# CoopCommand_2020-07-27_09-00-17.net
KiCad netlist of a schematic drawn in EasyEDA
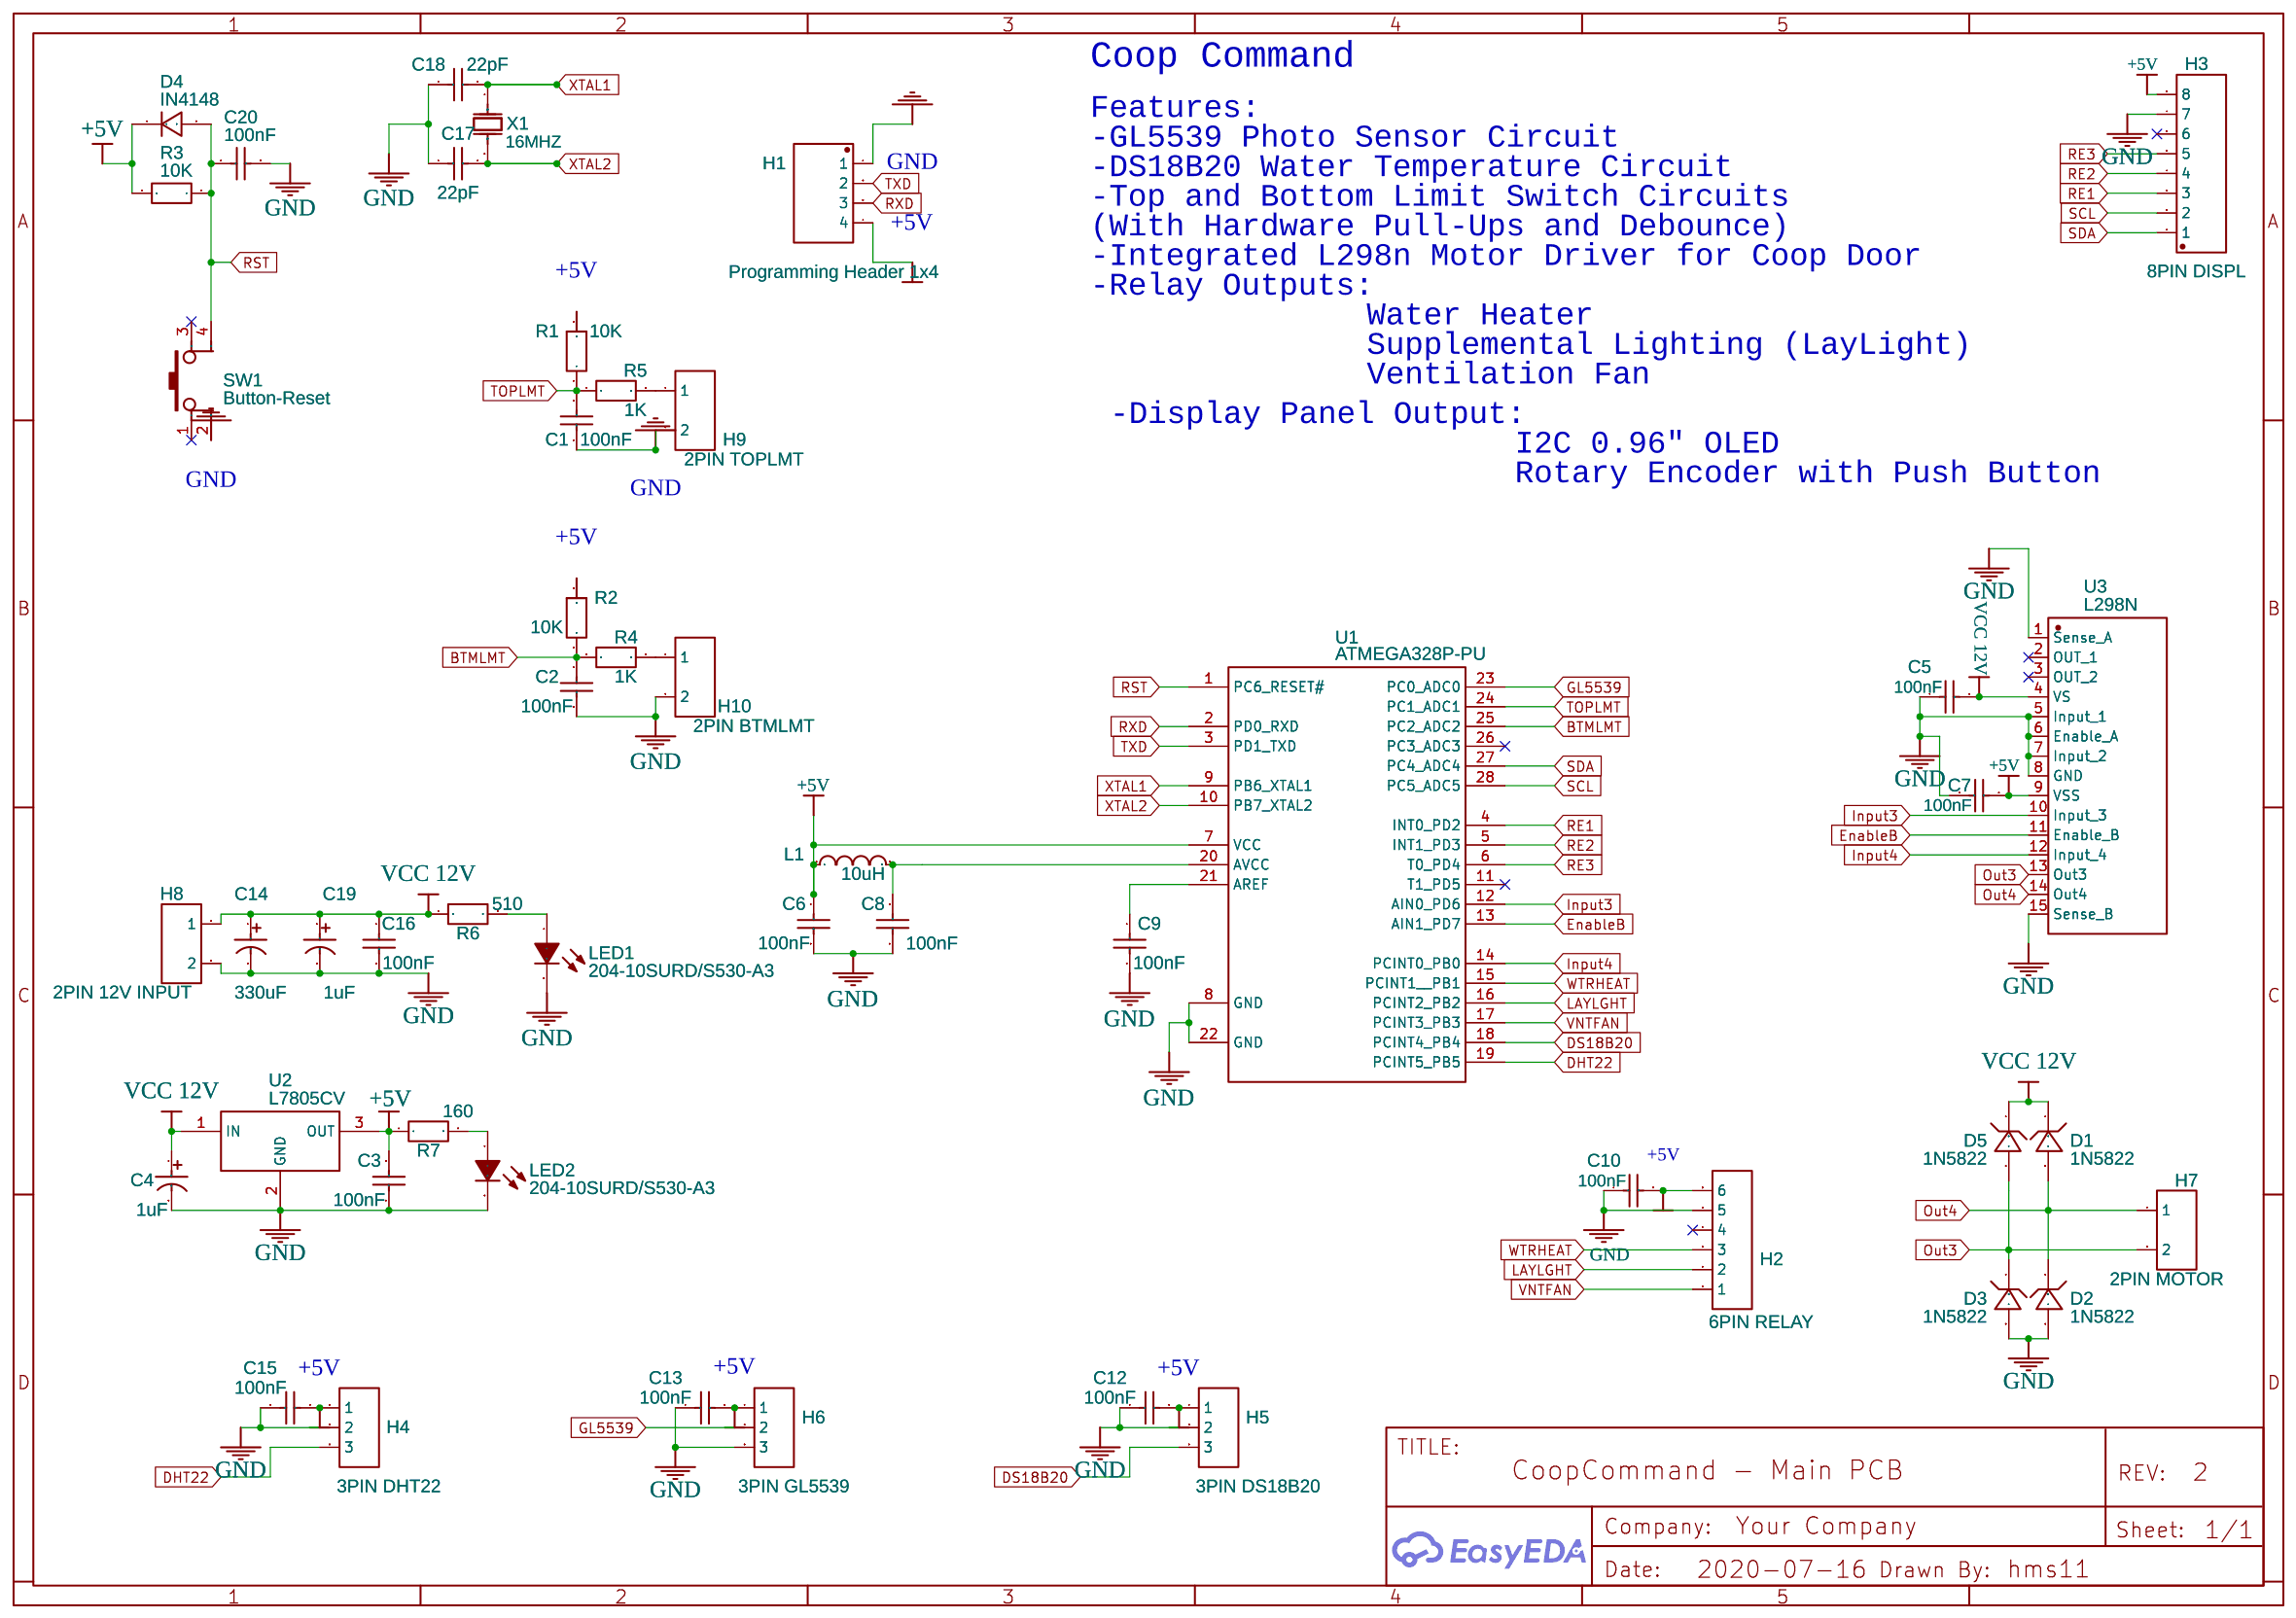
[diagram p0: schematic sheet]

(export (version "E")
  (design (tool "Eeschema 10.0.6"))
  (components
    (comp (ref "C1")
      (value "100nF")
      (fields
        (field (name "BOM_Manufacturer Part") "CS1F5.6Y5V1A104Z")
        (field (name "BOM_Supplier Part") "C9306")
      )
      (libsource (lib "") (part "CS1F5.6Y5V1A104Z_1"))
    )
    (comp (ref "C2")
      (value "100nF")
      (fields
        (field (name "BOM_Manufacturer Part") "CS1F5.6Y5V1A104Z")
        (field (name "BOM_Supplier Part") "C9306")
      )
      (libsource (lib "") (part "CS1F5.6Y5V1A104Z_1"))
    )
    (comp (ref "C3")
      (value "100nF")
      (fields
        (field (name "BOM_Manufacturer Part") "CS1F5.6Y5V1A104Z")
        (field (name "BOM_Supplier Part") "C9306")
      )
      (libsource (lib "") (part "CS1F5.6Y5V1A104Z_1"))
    )
    (comp (ref "C4")
      (value "1uF")
      (fields
        (field (name "BOM_Manufacturer Part") "1uF 50V 4*5")
        (field (name "BOM_Supplier Part") "C47848")
      )
      (libsource (lib "") (part "1uF 50V 4*5"))
    )
    (comp (ref "C5")
      (value "100nF")
      (fields
        (field (name "BOM_Manufacturer Part") "CS1F5.6Y5V1A104Z")
        (field (name "BOM_Supplier Part") "C9306")
      )
      (libsource (lib "") (part "CS1F5.6Y5V1A104Z"))
    )
    (comp (ref "C6")
      (value "100nF")
      (fields
        (field (name "BOM_Manufacturer Part") "CS1F5.6Y5V1A104Z")
        (field (name "BOM_Supplier Part") "C9306")
      )
      (libsource (lib "") (part "CS1F5.6Y5V1A104Z_1"))
    )
    (comp (ref "C7")
      (value "100nF")
      (fields
        (field (name "BOM_Manufacturer Part") "CS1F5.6Y5V1A104Z")
        (field (name "BOM_Supplier Part") "C9306")
      )
      (libsource (lib "") (part "CS1F5.6Y5V1A104Z"))
    )
    (comp (ref "C8")
      (value "100nF")
      (fields
        (field (name "BOM_Manufacturer Part") "CS1F5.6Y5V1A104Z")
        (field (name "BOM_Supplier Part") "C9306")
      )
      (libsource (lib "") (part "CS1F5.6Y5V1A104Z_1"))
    )
    (comp (ref "C9")
      (value "100nF")
      (fields
        (field (name "BOM_Manufacturer Part") "CS1F5.6Y5V1A104Z")
        (field (name "BOM_Supplier Part") "C9306")
      )
      (libsource (lib "") (part "CS1F5.6Y5V1A104Z_1"))
    )
    (comp (ref "C10")
      (value "100nF")
      (fields
        (field (name "BOM_Manufacturer Part") "CS1F5.6Y5V1A104Z")
        (field (name "BOM_Supplier Part") "C9306")
      )
      (libsource (lib "") (part "CS1F5.6Y5V1A104Z"))
    )
    (comp (ref "C12")
      (value "100nF")
      (fields
        (field (name "BOM_Manufacturer Part") "CS1F5.6Y5V1A104Z")
        (field (name "BOM_Supplier Part") "C9306")
      )
      (libsource (lib "") (part "CS1F5.6Y5V1A104Z"))
    )
    (comp (ref "C13")
      (value "100nF")
      (fields
        (field (name "BOM_Manufacturer Part") "CS1F5.6Y5V1A104Z")
        (field (name "BOM_Supplier Part") "C9306")
      )
      (libsource (lib "") (part "CS1F5.6Y5V1A104Z"))
    )
    (comp (ref "C14")
      (value "330uF")
      (fields
        (field (name "BOM_Manufacturer Part") "330uF 50V 10*17")
        (field (name "BOM_Supplier Part") "C45107")
      )
      (libsource (lib "") (part "330uF 50V 10*17"))
    )
    (comp (ref "C15")
      (value "100nF")
      (fields
        (field (name "BOM_Manufacturer Part") "CS1F5.6Y5V1A104Z")
        (field (name "BOM_Supplier Part") "C9306")
      )
      (libsource (lib "") (part "CS1F5.6Y5V1A104Z"))
    )
    (comp (ref "C16")
      (value "100nF")
      (fields
        (field (name "BOM_Manufacturer Part") "CS1F5.6Y5V1A104Z")
        (field (name "BOM_Supplier Part") "C9306")
      )
      (libsource (lib "") (part "CS1F5.6Y5V1A104Z_1"))
    )
    (comp (ref "C17")
      (value "22pF")
      (fields
        (field (name "BOM_Manufacturer Part") "22pf/50V 10%")
        (field (name "BOM_Supplier Part") "C9316")
      )
      (libsource (lib "") (part "22pf/50V 10%"))
    )
    (comp (ref "C18")
      (value "22pF")
      (fields
        (field (name "BOM_Manufacturer Part") "22pf/50V 10%")
        (field (name "BOM_Supplier Part") "C9316")
      )
      (libsource (lib "") (part "22pf/50V 10%"))
    )
    (comp (ref "C19")
      (value "1uF")
      (fields
        (field (name "BOM_Manufacturer Part") "1uF 50V 4*5")
        (field (name "BOM_Supplier Part") "C47848")
      )
      (libsource (lib "") (part "1uF 50V 4*5"))
    )
    (comp (ref "C20")
      (value "100nF")
      (fields
        (field (name "BOM_Manufacturer Part") "CS1F5.6Y5V1A104Z")
        (field (name "BOM_Supplier Part") "C9306")
      )
      (libsource (lib "") (part "CS1F5.6Y5V1A104Z"))
    )
    (comp (ref "D1")
      (value "1N5822")
      (fields (field (name "BOM_Supplier Part") "C402220"))
      (libsource (lib "") (part "1N5822_C402220_1"))
    )
    (comp (ref "D2")
      (value "1N5822")
      (fields (field (name "BOM_Supplier Part") "C402220"))
      (libsource (lib "") (part "1N5822_C402220_1"))
    )
    (comp (ref "D3")
      (value "1N5822")
      (fields (field (name "BOM_Supplier Part") "C402220"))
      (libsource (lib "") (part "1N5822_C402220"))
    )
    (comp (ref "D4")
      (value "IN4148")
      (fields (field (name "BOM_Supplier Part") "C14538"))
      (libsource (lib "") (part "IN4148"))
    )
    (comp (ref "D5")
      (value "1N5822")
      (fields (field (name "BOM_Supplier Part") "C402220"))
      (libsource (lib "") (part "1N5822_C402220"))
    )
    (comp (ref "H1")
      (value "Programming Header 1x4")
      (fields
        (field (name "BOM_Manufacturer Part") "210S-1*4P L=11.6MMGold-plated black")
        (field (name "BOM_Supplier Part") "C124378")
      )
      (libsource (lib "") (part "Header-Male-2.54_1x4"))
    )
    (comp (ref "H2")
      (value "6PIN RELAY")
      (fields
        (field (name "BOM_Manufacturer Part") "Header-Male-2.54_1x6")
        (field (name "BOM_Supplier Part") "C37208")
      )
      (libsource (lib "") (part "Header-Male-2.54_1x6"))
    )
    (comp (ref "H3")
      (value "8PIN DISPL")
      (fields
        (field (name "BOM_Manufacturer Part") "210S-1*8P L=11.6MMGold-plated black")
        (field (name "BOM_Supplier Part") "C124381")
      )
      (libsource (lib "") (part "Header-Male-2.54_1x8"))
    )
    (comp (ref "H4")
      (value "3PIN DHT22")
      (fields
        (field (name "BOM_Manufacturer Part") "Header2.54mm 1*3P")
        (field (name "BOM_Supplier Part") "C49257")
      )
      (libsource (lib "") (part "Header-Male-2.54_1x3"))
    )
    (comp (ref "H5")
      (value "3PIN DS18B20")
      (fields
        (field (name "BOM_Manufacturer Part") "Header2.54mm 1*3P")
        (field (name "BOM_Supplier Part") "C49257")
      )
      (libsource (lib "") (part "Header-Male-2.54_1x3"))
    )
    (comp (ref "H6")
      (value "3PIN GL5539")
      (fields
        (field (name "BOM_Manufacturer Part") "Header2.54mm 1*3P")
        (field (name "BOM_Supplier Part") "C49257")
      )
      (libsource (lib "") (part "Header-Male-2.54_1x3"))
    )
    (comp (ref "H7")
      (value "2PIN MOTOR")
      (fields (field (name "BOM_Manufacturer Part") "826629-2") (field (name "BOM_Supplier Part") "C86471"))
      (libsource (lib "") (part "Header-Male-2.54_1x2"))
    )
    (comp (ref "H8")
      (value "2PIN 12V INPUT")
      (fields (field (name "BOM_Manufacturer Part") "826629-2") (field (name "BOM_Supplier Part") "C86471"))
      (libsource (lib "") (part "Header-Male-2.54_1x2_1"))
    )
    (comp (ref "H9")
      (value "2PIN TOPLMT")
      (fields (field (name "BOM_Manufacturer Part") "826629-2") (field (name "BOM_Supplier Part") "C86471"))
      (libsource (lib "") (part "Header-Male-2.54_1x2"))
    )
    (comp (ref "H10")
      (value "2PIN BTMLMT")
      (fields (field (name "BOM_Manufacturer Part") "826629-2") (field (name "BOM_Supplier Part") "C86471"))
      (libsource (lib "") (part "Header-Male-2.54_1x2"))
    )
    (comp (ref "L1")
      (value "10uH")
      (fields
        (field (name "BOM_Manufacturer Part") "LGA0307-100KP52E")
        (field (name "BOM_Supplier Part") "C84773")
      )
      (libsource (lib "") (part "LGA0307-100KP52E"))
    )
    (comp (ref "LED1")
      (value "204-10SURD/S530-A3")
      (fields (field (name "BOM_Supplier Part") "C99772"))
      (libsource (lib "") (part "204-10SURD/S530-A3"))
    )
    (comp (ref "LED2")
      (value "204-10SURD/S530-A3")
      (fields (field (name "BOM_Supplier Part") "C99772"))
      (libsource (lib "") (part "204-10SURD/S530-A3"))
    )
    (comp (ref "R1")
      (value "10K")
      (fields
        (field (name "BOM_Manufacturer Part") "RN 1/4W 10K F T/B A1")
        (field (name "BOM_Supplier Part") "C410695")
      )
      (libsource (lib "") (part "RN 1/4W 10K F T/B A1"))
    )
    (comp (ref "R2")
      (value "10K")
      (fields
        (field (name "BOM_Manufacturer Part") "RN 1/4W 10K F T/B A1")
        (field (name "BOM_Supplier Part") "C410695")
      )
      (libsource (lib "") (part "RN 1/4W 10K F T/B A1"))
    )
    (comp (ref "R3")
      (value "10K")
      (fields
        (field (name "BOM_Manufacturer Part") "RN 1/4W 10K F T/B A1")
        (field (name "BOM_Supplier Part") "C410695")
      )
      (libsource (lib "") (part "RN 1/4W 10K F T/B A1_1"))
    )
    (comp (ref "R4")
      (value "1K")
      (fields
        (field (name "BOM_Manufacturer Part") "RN 1/4W 1K F T/B A1")
        (field (name "BOM_Supplier Part") "C410696")
      )
      (libsource (lib "") (part "RN 1/4W 1K F T/B A1"))
    )
    (comp (ref "R5")
      (value "1K")
      (fields
        (field (name "BOM_Manufacturer Part") "RN 1/4W 1K F T/B A1")
        (field (name "BOM_Supplier Part") "C410696")
      )
      (libsource (lib "") (part "RN 1/4W 1K F T/B A1"))
    )
    (comp (ref "R6")
      (value "510")
      (fields
        (field (name "BOM_Manufacturer Part") "RN 1/2WS 510R F T/B A1")
        (field (name "BOM_Supplier Part") "C433511")
      )
      (libsource (lib "") (part "RN 1/2WS 510R F T/B A1"))
    )
    (comp (ref "R7")
      (value "160")
      (fields
        (field (name "BOM_Manufacturer Part") "RN 1/4W 160R F T/B A1")
        (field (name "BOM_Supplier Part") "C410672")
      )
      (libsource (lib "") (part "RN 1/4W 160R F T/B A1"))
    )
    (comp (ref "SW1")
      (value "Button-Reset")
      (fields
        (field (name "BOM_Manufacturer Part") "Switch,6*6*6Plastic head,260G, 0.25mm,Straight line")
        (field (name "BOM_Supplier Part") "C71836")
      )
      (libsource (lib "") (part "Button-6x6x6mm"))
    )
    (comp (ref "U1")
      (value "ATMEGA328P-PU")
      (fields (field (name "BOM_Supplier Part") "C33901"))
      (libsource (lib "") (part "ATMEGA328P-PU"))
    )
    (comp (ref "U2")
      (value "L7805CV")
      (fields (field (name "BOM_Supplier Part") "C111887"))
      (libsource (lib "") (part "L7805CV"))
    )
    (comp (ref "U3")
      (value "L298N")
      (fields (field (name "BOM_Supplier Part") "C434589"))
      (libsource (lib "") (part "L298N"))
    )
    (comp (ref "X1")
      (value "16MHZ")
      (fields
        (field (name "BOM_Manufacturer Part") "5S0-1600A1620-00")
        (field (name "BOM_Supplier Part") "C389708")
      )
      (libsource (lib "") (part "5S0-1600A1620-00"))
    )
  )
  (nets
    (net (code "1") (name "+5V") (class "Default")
      (node (ref "C10") (pin "2") (pinfunction "2_2") (pintype "input"))
      (node (ref "C12") (pin "2") (pinfunction "2_2") (pintype "input"))
      (node (ref "C13") (pin "2") (pinfunction "2_2") (pintype "input"))
      (node (ref "C15") (pin "2") (pinfunction "2_2") (pintype "input"))
      (node (ref "C3") (pin "1") (pinfunction "1_1") (pintype "input"))
      (node (ref "C6") (pin "1") (pinfunction "1_1") (pintype "input"))
      (node (ref "C7") (pin "2") (pinfunction "2_2") (pintype "input"))
      (node (ref "D4") (pin "1") (pinfunction "1_1") (pintype "unspecified"))
      (node (ref "H1") (pin "4") (pinfunction "4_4") (pintype "unspecified"))
      (node (ref "H2") (pin "6") (pinfunction "6_6") (pintype "input"))
      (node (ref "H3") (pin "8") (pinfunction "8_8") (pintype "unspecified"))
      (node (ref "H4") (pin "1") (pinfunction "1_1") (pintype "input"))
      (node (ref "H5") (pin "1") (pinfunction "1_1") (pintype "input"))
      (node (ref "H6") (pin "1") (pinfunction "1_1") (pintype "input"))
      (node (ref "L1") (pin "1") (pinfunction "1_1") (pintype "unspecified"))
      (node (ref "R1") (pin "2") (pinfunction "2_2") (pintype "unspecified"))
      (node (ref "R2") (pin "2") (pinfunction "2_2") (pintype "unspecified"))
      (node (ref "R3") (pin "2") (pinfunction "2_2") (pintype "unspecified"))
      (node (ref "R7") (pin "1") (pinfunction "1_1") (pintype "unspecified"))
      (node (ref "U1") (pin "7") (pinfunction "VCC_7") (pintype "passive"))
      (node (ref "U2") (pin "3") (pinfunction "OUT_3") (pintype "passive"))
      (node (ref "U3") (pin "9") (pinfunction "VSS_9") (pintype "unspecified"))
    )
    (net (code "2") (name "BTMLMT") (class "Default")
      (node (ref "C2") (pin "1") (pinfunction "1_1") (pintype "input"))
      (node (ref "R2") (pin "1") (pinfunction "1_1") (pintype "unspecified"))
      (node (ref "R4") (pin "1") (pinfunction "1_1") (pintype "unspecified"))
      (node (ref "U1") (pin "25") (pinfunction "PC2_ADC2_25") (pintype "bidirectional"))
    )
    (net (code "3") (name "DHT22") (class "Default")
      (node (ref "H4") (pin "3") (pinfunction "3_3") (pintype "input"))
      (node (ref "U1") (pin "19") (pinfunction "PCINT5_PB5_19") (pintype "bidirectional"))
    )
    (net (code "4") (name "DS18B20") (class "Default")
      (node (ref "H5") (pin "3") (pinfunction "3_3") (pintype "input"))
      (node (ref "U1") (pin "18") (pinfunction "PCINT4_PB4_18") (pintype "bidirectional"))
    )
    (net (code "5") (name "EnableB") (class "Default")
      (node (ref "U1") (pin "13") (pinfunction "AIN1_PD7_13") (pintype "bidirectional"))
      (node (ref "U3") (pin "11") (pinfunction "Enable_B_11") (pintype "unspecified"))
    )
    (net (code "6") (name "GL5539") (class "Default")
      (node (ref "H6") (pin "2") (pinfunction "2_2") (pintype "input"))
      (node (ref "U1") (pin "23") (pinfunction "PC0_ADC0_23") (pintype "bidirectional"))
    )
    (net (code "7") (name "GND") (class "Default")
      (node (ref "C1") (pin "2") (pinfunction "2_2") (pintype "input"))
      (node (ref "C10") (pin "1") (pinfunction "1_1") (pintype "input"))
      (node (ref "C12") (pin "1") (pinfunction "1_1") (pintype "input"))
      (node (ref "C13") (pin "1") (pinfunction "1_1") (pintype "input"))
      (node (ref "C14") (pin "2") (pinfunction "2_2") (pintype "input"))
      (node (ref "C15") (pin "1") (pinfunction "1_1") (pintype "input"))
      (node (ref "C16") (pin "2") (pinfunction "2_2") (pintype "input"))
      (node (ref "C17") (pin "1") (pinfunction "1_1") (pintype "input"))
      (node (ref "C18") (pin "1") (pinfunction "1_1") (pintype "input"))
      (node (ref "C19") (pin "2") (pinfunction "2_2") (pintype "input"))
      (node (ref "C2") (pin "2") (pinfunction "2_2") (pintype "input"))
      (node (ref "C20") (pin "2") (pinfunction "2_2") (pintype "input"))
      (node (ref "C3") (pin "2") (pinfunction "2_2") (pintype "input"))
      (node (ref "C4") (pin "2") (pinfunction "2_2") (pintype "input"))
      (node (ref "C5") (pin "1") (pinfunction "1_1") (pintype "input"))
      (node (ref "C6") (pin "2") (pinfunction "2_2") (pintype "input"))
      (node (ref "C7") (pin "1") (pinfunction "1_1") (pintype "input"))
      (node (ref "C8") (pin "2") (pinfunction "2_2") (pintype "input"))
      (node (ref "C9") (pin "2") (pinfunction "2_2") (pintype "input"))
      (node (ref "D2") (pin "2") (pinfunction "A_2") (pintype "unspecified"))
      (node (ref "D3") (pin "2") (pinfunction "A_2") (pintype "unspecified"))
      (node (ref "H1") (pin "1") (pinfunction "1_1") (pintype "unspecified"))
      (node (ref "H10") (pin "2") (pinfunction "2_2") (pintype "unspecified"))
      (node (ref "H2") (pin "5") (pinfunction "5_5") (pintype "input"))
      (node (ref "H3") (pin "7") (pinfunction "7_7") (pintype "unspecified"))
      (node (ref "H4") (pin "2") (pinfunction "2_2") (pintype "input"))
      (node (ref "H5") (pin "2") (pinfunction "2_2") (pintype "input"))
      (node (ref "H6") (pin "3") (pinfunction "3_3") (pintype "input"))
      (node (ref "H8") (pin "2") (pinfunction "2_2") (pintype "unspecified"))
      (node (ref "H9") (pin "2") (pinfunction "2_2") (pintype "unspecified"))
      (node (ref "LED1") (pin "2") (pinfunction "K_2") (pintype "input"))
      (node (ref "LED2") (pin "2") (pinfunction "K_2") (pintype "input"))
      (node (ref "SW1") (pin "2") (pinfunction "2_2") (pintype "input"))
      (node (ref "U1") (pin "22") (pinfunction "GND_22") (pintype "passive"))
      (node (ref "U1") (pin "8") (pinfunction "GND_8") (pintype "passive"))
      (node (ref "U2") (pin "2") (pinfunction "GND_2") (pintype "passive"))
      (node (ref "U3") (pin "1") (pinfunction "Sense_A_1") (pintype "unspecified"))
      (node (ref "U3") (pin "15") (pinfunction "Sense_B_15") (pintype "unspecified"))
      (node (ref "U3") (pin "5") (pinfunction "Input_1_5") (pintype "unspecified"))
      (node (ref "U3") (pin "6") (pinfunction "Enable_A_6") (pintype "unspecified"))
      (node (ref "U3") (pin "7") (pinfunction "Input_2_7") (pintype "unspecified"))
      (node (ref "U3") (pin "8") (pinfunction "GND_8") (pintype "unspecified"))
    )
    (net (code "8") (name "Input3") (class "Default")
      (node (ref "U1") (pin "12") (pinfunction "AIN0_PD6_12") (pintype "bidirectional"))
      (node (ref "U3") (pin "10") (pinfunction "Input_3_10") (pintype "unspecified"))
    )
    (net (code "9") (name "Input4") (class "Default")
      (node (ref "U1") (pin "14") (pinfunction "PCINT0_PB0_14") (pintype "bidirectional"))
      (node (ref "U3") (pin "12") (pinfunction "Input_4_12") (pintype "unspecified"))
    )
    (net (code "10") (name "LAYLGHT") (class "Default")
      (node (ref "H2") (pin "2") (pinfunction "2_2") (pintype "input"))
      (node (ref "U1") (pin "16") (pinfunction "PCINT2_PB2_16") (pintype "bidirectional"))
    )
    (net (code "11") (name "Net-(H9-Pad1)") (class "Default")
      (node (ref "H9") (pin "1") (pinfunction "1_1") (pintype "unspecified"))
      (node (ref "R5") (pin "2") (pinfunction "2_2") (pintype "unspecified"))
    )
    (net (code "12") (name "Net-(H10-Pad1)") (class "Default")
      (node (ref "H10") (pin "1") (pinfunction "1_1") (pintype "unspecified"))
      (node (ref "R4") (pin "2") (pinfunction "2_2") (pintype "unspecified"))
    )
    (net (code "13") (name "Net-(LED1-A)") (class "Default")
      (node (ref "LED1") (pin "1") (pinfunction "A_1") (pintype "input"))
      (node (ref "R6") (pin "2") (pinfunction "2_2") (pintype "unspecified"))
    )
    (net (code "14") (name "Net-(LED2-A)") (class "Default")
      (node (ref "LED2") (pin "1") (pinfunction "A_1") (pintype "input"))
      (node (ref "R7") (pin "2") (pinfunction "2_2") (pintype "unspecified"))
    )
    (net (code "15") (name "Net-(U1-AREF)") (class "Default")
      (node (ref "C9") (pin "1") (pinfunction "1_1") (pintype "input"))
      (node (ref "U1") (pin "21") (pinfunction "AREF_21") (pintype "passive"))
    )
    (net (code "16") (name "Net-(U1-AVCC)") (class "Default")
      (node (ref "C8") (pin "1") (pinfunction "1_1") (pintype "input"))
      (node (ref "L1") (pin "2") (pinfunction "2_2") (pintype "unspecified"))
      (node (ref "U1") (pin "20") (pinfunction "AVCC_20") (pintype "passive"))
    )
    (net (code "17") (name "Out3") (class "Default")
      (node (ref "D3") (pin "1") (pinfunction "C_1") (pintype "unspecified"))
      (node (ref "D5") (pin "2") (pinfunction "A_2") (pintype "unspecified"))
      (node (ref "H7") (pin "2") (pinfunction "2_2") (pintype "unspecified"))
      (node (ref "U3") (pin "13") (pinfunction "Out3_13") (pintype "unspecified"))
    )
    (net (code "18") (name "Out4") (class "Default")
      (node (ref "D1") (pin "2") (pinfunction "A_2") (pintype "unspecified"))
      (node (ref "D2") (pin "1") (pinfunction "C_1") (pintype "unspecified"))
      (node (ref "H7") (pin "1") (pinfunction "1_1") (pintype "unspecified"))
      (node (ref "U3") (pin "14") (pinfunction "Out4_14") (pintype "unspecified"))
    )
    (net (code "19") (name "RE1") (class "Default")
      (node (ref "H3") (pin "3") (pinfunction "3_3") (pintype "unspecified"))
      (node (ref "U1") (pin "4") (pinfunction "INT0_PD2_4") (pintype "bidirectional"))
    )
    (net (code "20") (name "RE2") (class "Default")
      (node (ref "H3") (pin "4") (pinfunction "4_4") (pintype "unspecified"))
      (node (ref "U1") (pin "5") (pinfunction "INT1_PD3_5") (pintype "bidirectional"))
    )
    (net (code "21") (name "RE3") (class "Default")
      (node (ref "H3") (pin "5") (pinfunction "5_5") (pintype "unspecified"))
      (node (ref "U1") (pin "6") (pinfunction "T0_PD4_6") (pintype "bidirectional"))
    )
    (net (code "22") (name "RST") (class "Default")
      (node (ref "C20") (pin "1") (pinfunction "1_1") (pintype "input"))
      (node (ref "D4") (pin "2") (pinfunction "2_2") (pintype "unspecified"))
      (node (ref "R3") (pin "1") (pinfunction "1_1") (pintype "unspecified"))
      (node (ref "SW1") (pin "4") (pinfunction "4_4") (pintype "input"))
      (node (ref "U1") (pin "1") (pinfunction "PC6_RESET#_1") (pintype "bidirectional"))
    )
    (net (code "23") (name "RXD") (class "Default")
      (node (ref "H1") (pin "3") (pinfunction "3_3") (pintype "unspecified"))
      (node (ref "U1") (pin "2") (pinfunction "PD0_RXD_2") (pintype "bidirectional"))
    )
    (net (code "24") (name "SCL") (class "Default")
      (node (ref "H3") (pin "2") (pinfunction "2_2") (pintype "unspecified"))
      (node (ref "U1") (pin "28") (pinfunction "PC5_ADC5_28") (pintype "bidirectional"))
    )
    (net (code "25") (name "SDA") (class "Default")
      (node (ref "H3") (pin "1") (pinfunction "1_1") (pintype "unspecified"))
      (node (ref "U1") (pin "27") (pinfunction "PC4_ADC4_27") (pintype "bidirectional"))
    )
    (net (code "26") (name "TOPLMT") (class "Default")
      (node (ref "C1") (pin "1") (pinfunction "1_1") (pintype "input"))
      (node (ref "R1") (pin "1") (pinfunction "1_1") (pintype "unspecified"))
      (node (ref "R5") (pin "1") (pinfunction "1_1") (pintype "unspecified"))
      (node (ref "U1") (pin "24") (pinfunction "PC1_ADC1_24") (pintype "bidirectional"))
    )
    (net (code "27") (name "TXD") (class "Default")
      (node (ref "H1") (pin "2") (pinfunction "2_2") (pintype "unspecified"))
      (node (ref "U1") (pin "3") (pinfunction "PD1_TXD_3") (pintype "bidirectional"))
    )
    (net (code "28") (name "VCC 12V") (class "Default")
      (node (ref "C14") (pin "1") (pinfunction "1_1") (pintype "input"))
      (node (ref "C16") (pin "1") (pinfunction "1_1") (pintype "input"))
      (node (ref "C19") (pin "1") (pinfunction "1_1") (pintype "input"))
      (node (ref "C4") (pin "1") (pinfunction "1_1") (pintype "input"))
      (node (ref "C5") (pin "2") (pinfunction "2_2") (pintype "input"))
      (node (ref "D1") (pin "1") (pinfunction "C_1") (pintype "unspecified"))
      (node (ref "D5") (pin "1") (pinfunction "C_1") (pintype "unspecified"))
      (node (ref "H8") (pin "1") (pinfunction "1_1") (pintype "unspecified"))
      (node (ref "R6") (pin "1") (pinfunction "1_1") (pintype "unspecified"))
      (node (ref "U2") (pin "1") (pinfunction "IN_1") (pintype "passive"))
      (node (ref "U3") (pin "4") (pinfunction "VS_4") (pintype "unspecified"))
    )
    (net (code "29") (name "VNTFAN") (class "Default")
      (node (ref "H2") (pin "1") (pinfunction "1_1") (pintype "input"))
      (node (ref "U1") (pin "17") (pinfunction "PCINT3_PB3_17") (pintype "bidirectional"))
    )
    (net (code "30") (name "WTRHEAT") (class "Default")
      (node (ref "H2") (pin "3") (pinfunction "3_3") (pintype "input"))
      (node (ref "U1") (pin "15") (pinfunction "PCINT1__PB1_15") (pintype "bidirectional"))
    )
    (net (code "31") (name "XTAL1") (class "Default")
      (node (ref "C18") (pin "2") (pinfunction "2_2") (pintype "input"))
      (node (ref "U1") (pin "9") (pinfunction "PB6_XTAL1_9") (pintype "bidirectional"))
      (node (ref "X1") (pin "1") (pinfunction "OSC1_1") (pintype "input"))
    )
    (net (code "32") (name "XTAL2") (class "Default")
      (node (ref "C17") (pin "2") (pinfunction "2_2") (pintype "input"))
      (node (ref "U1") (pin "10") (pinfunction "PB7_XTAL2_10") (pintype "bidirectional"))
      (node (ref "X1") (pin "2") (pinfunction "OSC2_2") (pintype "input"))
    )
    (net (code "33") (name "unconnected-(H2-Pad4)") (class "Default")
      (node (ref "H2") (pin "4") (pinfunction "4_4") (pintype "input+no_connect"))
    )
    (net (code "34") (name "unconnected-(H3-Pad6)") (class "Default")
      (node (ref "H3") (pin "6") (pinfunction "6_6") (pintype "unspecified+no_connect"))
    )
    (net (code "35") (name "unconnected-(SW1-Pad1)") (class "Default")
      (node (ref "SW1") (pin "1") (pinfunction "1_1") (pintype "input+no_connect"))
    )
    (net (code "36") (name "unconnected-(SW1-Pad3)") (class "Default")
      (node (ref "SW1") (pin "3") (pinfunction "3_3") (pintype "input+no_connect"))
    )
    (net (code "37") (name "unconnected-(U1-PC3_ADC3-Pad26)") (class "Default")
      (node (ref "U1") (pin "26") (pinfunction "PC3_ADC3_26") (pintype "bidirectional+no_connect"))
    )
    (net (code "38") (name "unconnected-(U1-T1_PD5-Pad11)") (class "Default")
      (node (ref "U1") (pin "11") (pinfunction "T1_PD5_11") (pintype "bidirectional+no_connect"))
    )
    (net (code "39") (name "unconnected-(U3-OUT_1-Pad2)") (class "Default")
      (node (ref "U3") (pin "2") (pinfunction "OUT_1_2") (pintype "unspecified+no_connect"))
    )
    (net (code "40") (name "unconnected-(U3-OUT_2-Pad3)") (class "Default")
      (node (ref "U3") (pin "3") (pinfunction "OUT_2_3") (pintype "unspecified+no_connect"))
    )
  )
)
